# MOM-LED-v06.net
KiCad netlist of a schematic drawn in EAGLE
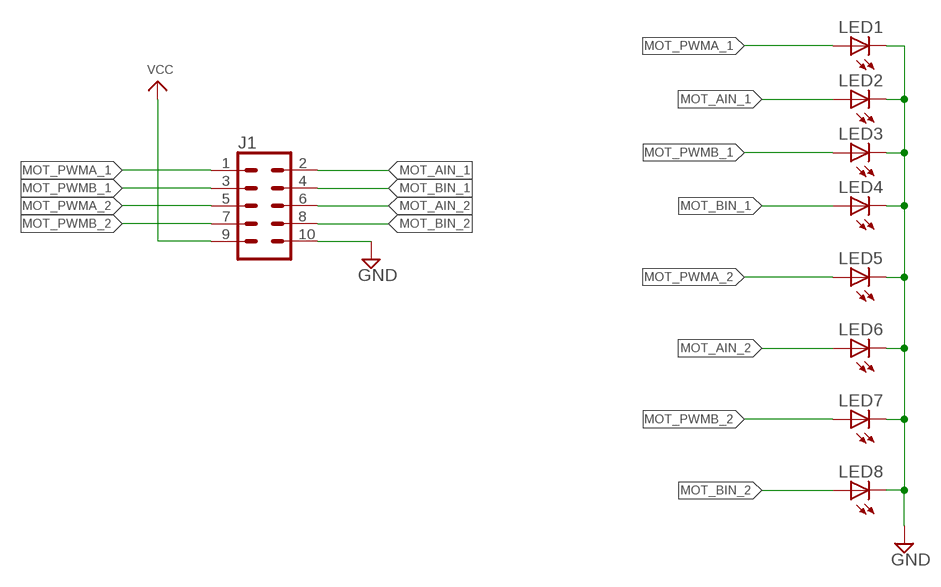
[diagram p0: schematic, sheet 1]

(export (version "E")
  (design (tool "Eeschema 10.0.6"))
  (components
    (comp (ref "J1")
      (value "CONN_05X2SHD_LOCK")
      (footprint "eagle-import:2X5-SHROUDED_LOCK")
      (libsource (lib "eagle-import") (part "CONN_05X2SHD_LOCK"))
    )
    (comp (ref "LED1")
      (value "LED5MM")
      (footprint "eagle-import:LED5MM")
      (libsource (lib "eagle-import") (part "LED5MM"))
    )
    (comp (ref "LED2")
      (value "LED5MM")
      (footprint "eagle-import:LED5MM")
      (libsource (lib "eagle-import") (part "LED5MM"))
    )
    (comp (ref "LED3")
      (value "LED5MM")
      (footprint "eagle-import:LED5MM")
      (libsource (lib "eagle-import") (part "LED5MM"))
    )
    (comp (ref "LED4")
      (value "LED5MM")
      (footprint "eagle-import:LED5MM")
      (libsource (lib "eagle-import") (part "LED5MM"))
    )
    (comp (ref "LED5")
      (value "LED5MM")
      (footprint "eagle-import:LED5MM")
      (libsource (lib "eagle-import") (part "LED5MM"))
    )
    (comp (ref "LED6")
      (value "LED5MM")
      (footprint "eagle-import:LED5MM")
      (libsource (lib "eagle-import") (part "LED5MM"))
    )
    (comp (ref "LED7")
      (value "LED5MM")
      (footprint "eagle-import:LED5MM")
      (libsource (lib "eagle-import") (part "LED5MM"))
    )
    (comp (ref "LED8")
      (value "LED5MM")
      (footprint "eagle-import:LED5MM")
      (libsource (lib "eagle-import") (part "LED5MM"))
    )
  )
  (nets
    (net (code "1") (name "GND") (class "Default")
      (node (ref "J1") (pin "10") (pinfunction "10_10") (pintype "passive"))
      (node (ref "LED1") (pin "K") (pinfunction "C_K") (pintype "passive"))
      (node (ref "LED2") (pin "K") (pinfunction "C_K") (pintype "passive"))
      (node (ref "LED3") (pin "K") (pinfunction "C_K") (pintype "passive"))
      (node (ref "LED4") (pin "K") (pinfunction "C_K") (pintype "passive"))
      (node (ref "LED5") (pin "K") (pinfunction "C_K") (pintype "passive"))
      (node (ref "LED6") (pin "K") (pinfunction "C_K") (pintype "passive"))
      (node (ref "LED7") (pin "K") (pinfunction "C_K") (pintype "passive"))
      (node (ref "LED8") (pin "K") (pinfunction "C_K") (pintype "passive"))
    )
    (net (code "2") (name "MOT_AIN_1") (class "Default")
      (node (ref "J1") (pin "2") (pinfunction "2_2") (pintype "passive"))
      (node (ref "LED2") (pin "A") (pinfunction "A_A") (pintype "passive"))
    )
    (net (code "3") (name "MOT_AIN_2") (class "Default")
      (node (ref "J1") (pin "6") (pinfunction "6_6") (pintype "passive"))
      (node (ref "LED6") (pin "A") (pinfunction "A_A") (pintype "passive"))
    )
    (net (code "4") (name "MOT_BIN_1") (class "Default")
      (node (ref "J1") (pin "4") (pinfunction "4_4") (pintype "passive"))
      (node (ref "LED4") (pin "A") (pinfunction "A_A") (pintype "passive"))
    )
    (net (code "5") (name "MOT_BIN_2") (class "Default")
      (node (ref "J1") (pin "8") (pinfunction "8_8") (pintype "passive"))
      (node (ref "LED8") (pin "A") (pinfunction "A_A") (pintype "passive"))
    )
    (net (code "6") (name "MOT_PWMA_1") (class "Default")
      (node (ref "J1") (pin "1") (pinfunction "1_1") (pintype "passive"))
      (node (ref "LED1") (pin "A") (pinfunction "A_A") (pintype "passive"))
    )
    (net (code "7") (name "MOT_PWMA_2") (class "Default")
      (node (ref "J1") (pin "5") (pinfunction "5_5") (pintype "passive"))
      (node (ref "LED5") (pin "A") (pinfunction "A_A") (pintype "passive"))
    )
    (net (code "8") (name "MOT_PWMB_1") (class "Default")
      (node (ref "J1") (pin "3") (pinfunction "3_3") (pintype "passive"))
      (node (ref "LED3") (pin "A") (pinfunction "A_A") (pintype "passive"))
    )
    (net (code "9") (name "MOT_PWMB_2") (class "Default")
      (node (ref "J1") (pin "7") (pinfunction "7_7") (pintype "passive"))
      (node (ref "LED7") (pin "A") (pinfunction "A_A") (pintype "passive"))
    )
    (net (code "10") (name "VCC") (class "Default")
      (node (ref "J1") (pin "9") (pinfunction "9_9") (pintype "passive"))
    )
  )
)
